# adc_dac_lo.net
KiCad netlist of a schematic drawn in Altium Designer
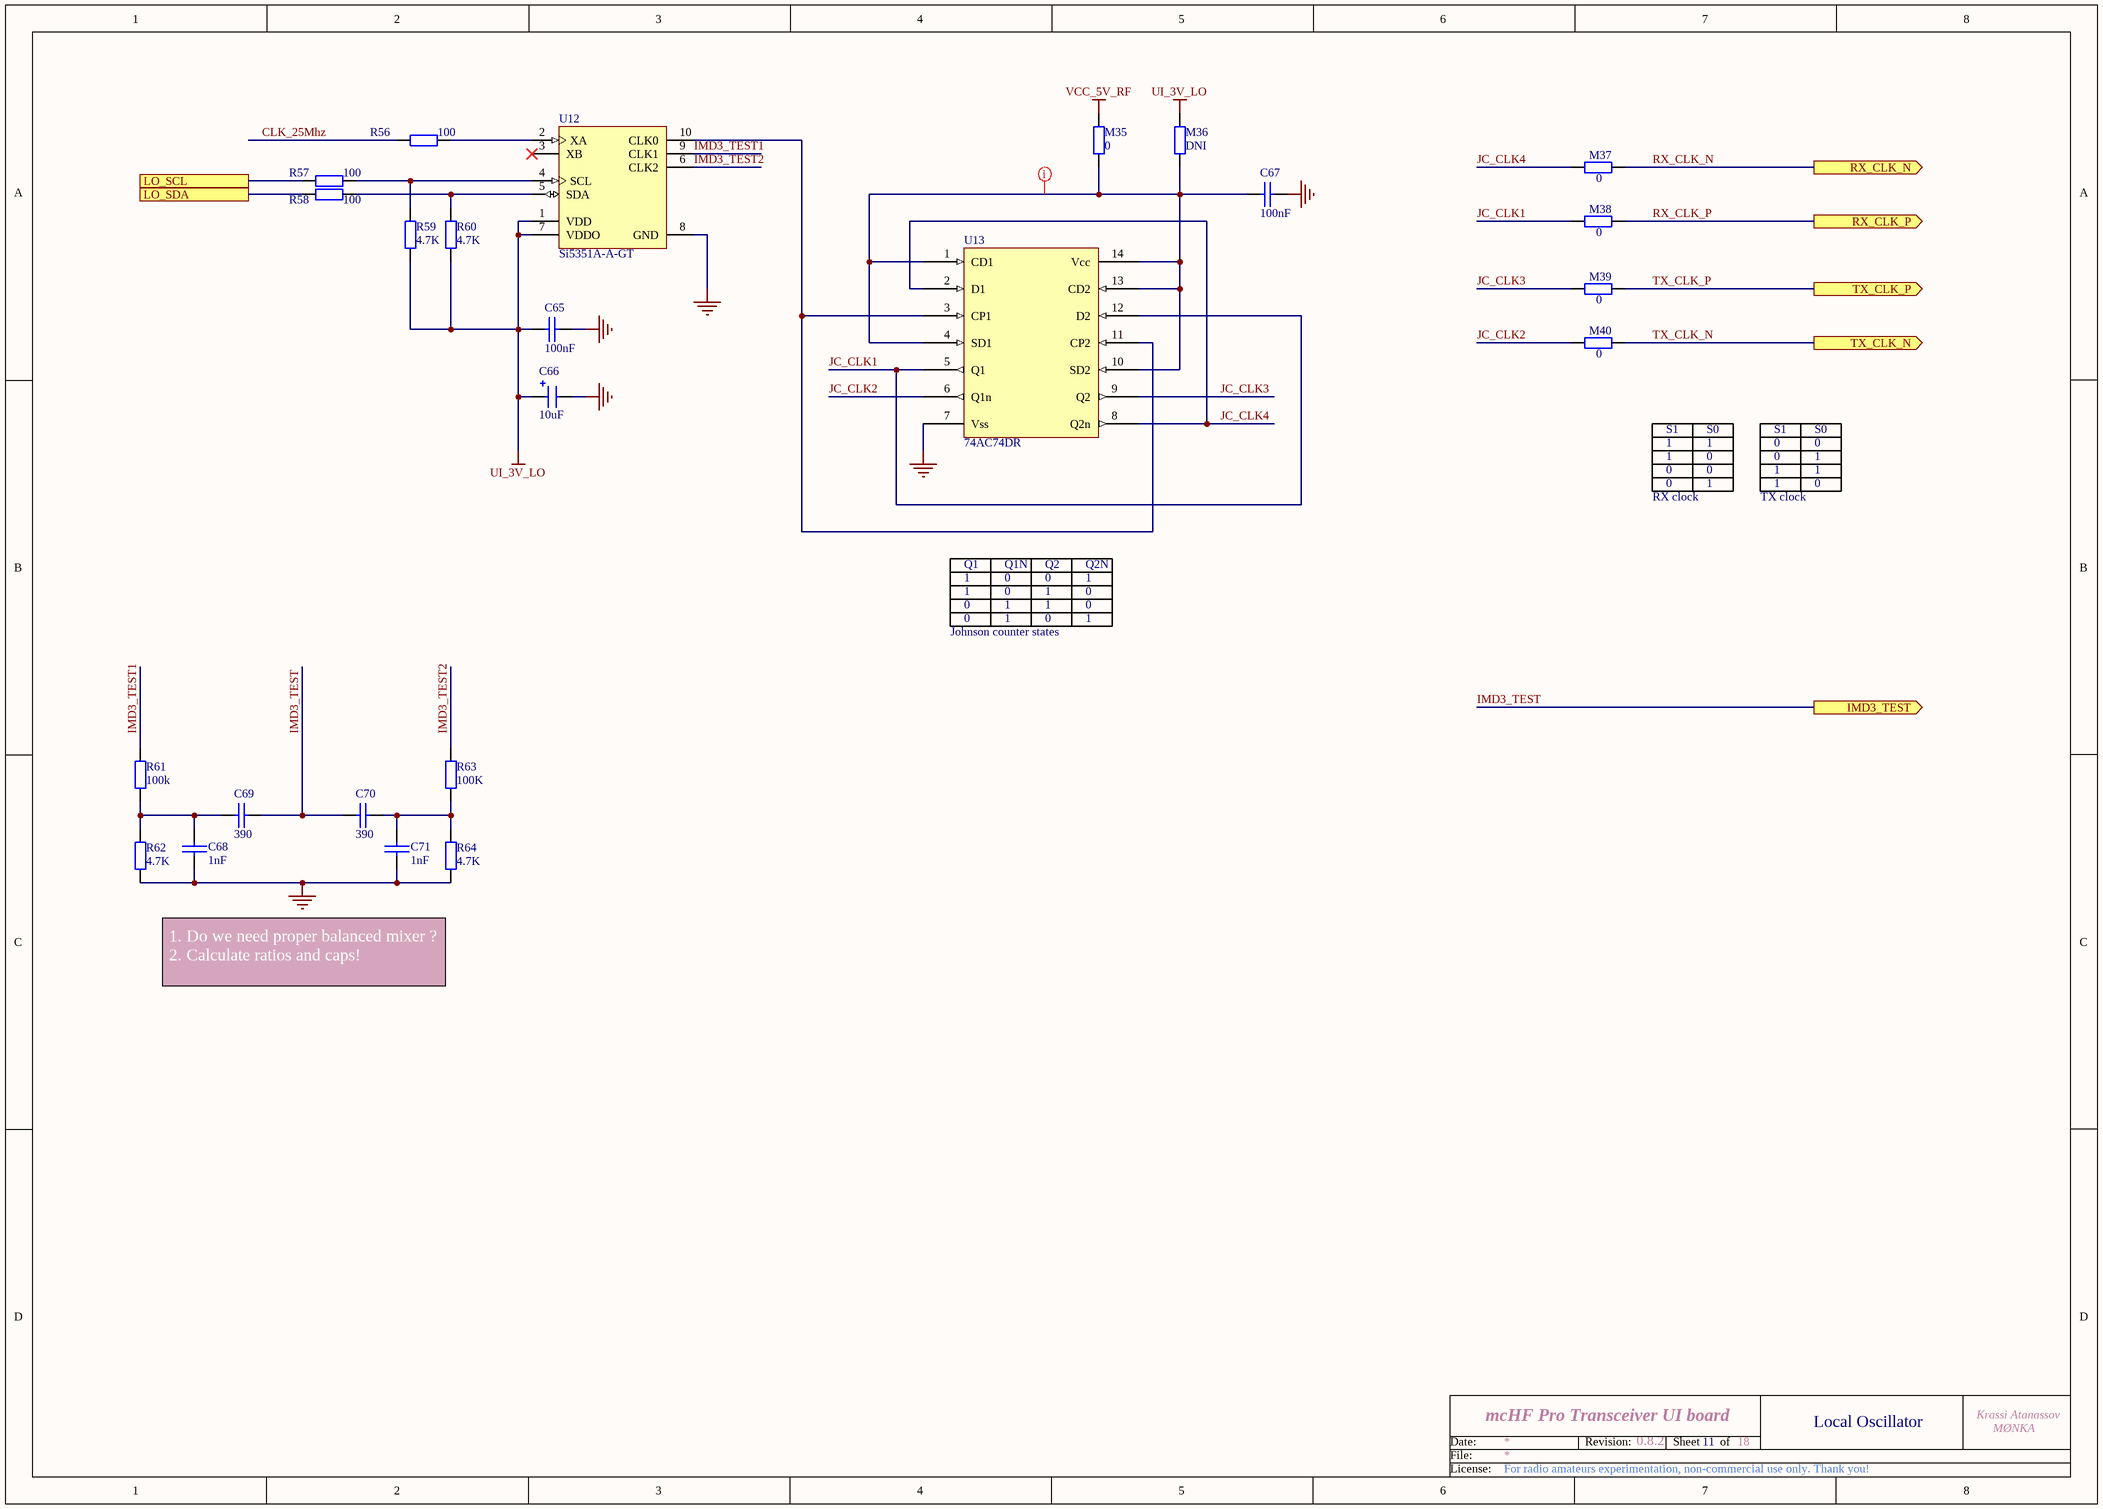
[diagram p0: adc_dac_lo.SchDoc]

(export (version "E")
  (design (tool "Eeschema 10.0.6"))
  (components
    (comp (ref "C65")
      (value "100nF")
      (footprint "0805")
      (description "Capacitor")
      (libsource (lib "*") (part "CAP"))
    )
    (comp (ref "C66")
      (value "10uF")
      (footprint "1206_Elec_Cap")
      (description "Electrolitic capacitor")
      (libsource (lib "*") (part "CAP-POL"))
    )
    (comp (ref "C67")
      (value "100nF")
      (footprint "0805")
      (description "Capacitor")
      (libsource (lib "*") (part "CAP"))
    )
    (comp (ref "C68")
      (value "1nF")
      (footprint "0805")
      (description "Capacitor")
      (libsource (lib "mcHF_ui") (part "CAP"))
    )
    (comp (ref "C69")
      (value "390")
      (footprint "0805")
      (description "Capacitor")
      (libsource (lib "mcHF_rf") (part "CAP"))
    )
    (comp (ref "C70")
      (value "390")
      (footprint "0805")
      (description "Capacitor")
      (libsource (lib "mcHF_rf") (part "CAP"))
    )
    (comp (ref "C71")
      (value "1nF")
      (footprint "0805")
      (description "Capacitor")
      (libsource (lib "mcHF_ui") (part "CAP"))
    )
    (comp (ref "M35")
      (value "0")
      (footprint "0805")
      (description "Resistor")
      (libsource (lib "mcHF_rf") (part "RES"))
    )
    (comp (ref "M36")
      (value "DNI")
      (footprint "0805")
      (description "Resistor")
      (libsource (lib "mcHF_rf") (part "RES"))
    )
    (comp (ref "M37")
      (value "0")
      (footprint "0805")
      (description "Resistor")
      (libsource (lib "") (part "RES_1"))
    )
    (comp (ref "M38")
      (value "0")
      (footprint "0805")
      (description "Resistor")
      (libsource (lib "") (part "RES_1"))
    )
    (comp (ref "M39")
      (value "0")
      (footprint "0805")
      (description "Resistor")
      (libsource (lib "") (part "RES_1"))
    )
    (comp (ref "M40")
      (value "0")
      (footprint "0805")
      (description "Resistor")
      (libsource (lib "") (part "RES_1"))
    )
    (comp (ref "R56")
      (value "100")
      (footprint "0805")
      (description "Resistor")
      (libsource (lib "*") (part "RES"))
    )
    (comp (ref "R57")
      (value "100")
      (footprint "0805")
      (description "Resistor")
      (libsource (lib "*") (part "RES"))
    )
    (comp (ref "R58")
      (value "100")
      (footprint "0805")
      (description "Resistor")
      (libsource (lib "*") (part "RES"))
    )
    (comp (ref "R59")
      (value "4.7K")
      (footprint "0805")
      (description "Resistor")
      (libsource (lib "") (part "RES_1"))
    )
    (comp (ref "R60")
      (value "4.7K")
      (footprint "0805")
      (description "Resistor")
      (libsource (lib "") (part "RES_1"))
    )
    (comp (ref "R61")
      (value "100k")
      (footprint "0805")
      (description "Resistor")
      (libsource (lib "") (part "RES_1"))
    )
    (comp (ref "R62")
      (value "4.7K")
      (footprint "0805")
      (description "Resistor")
      (libsource (lib "") (part "RES_1"))
    )
    (comp (ref "R63")
      (value "100K")
      (footprint "0805")
      (description "Resistor")
      (libsource (lib "") (part "RES_1"))
    )
    (comp (ref "R64")
      (value "4.7K")
      (footprint "0805")
      (description "Resistor")
      (libsource (lib "") (part "RES_1"))
    )
    (comp (ref "U12")
      (value "Si5351A-A-GT")
      (footprint "SLAB-MSOP-10_N")
      (fields (field (name "MANUFACTURER") "Silicon Labs"))
      (libsource (lib "Silicon Labs Clocks and Oscillators") (part "Si5351A-A-GT"))
    )
    (comp (ref "U13")
      (value "74AC74DR")
      (footprint "SO-14")
      (description "Low Voltage Dual D-Type Positive Edge-Triggered  Flip-Flop with 5V Tolerant Inputs")
      (libsource (lib "*") (part "74LCX74M"))
    )
  )
  (nets
    (net (code "1") (name "/CLK_25Mhz") (class "Default")
      (node (ref "R56") (pin "2") (pinfunction "2_2") (pintype "passive"))
    )
    (net (code "2") (name "/IMD3_TEST") (class "Default")
      (node (ref "C69") (pin "1") (pinfunction "1_1") (pintype "passive"))
      (node (ref "C70") (pin "2") (pinfunction "2_2") (pintype "passive"))
    )
    (net (code "3") (name "/IMD3_TEST1") (class "Default")
      (node (ref "R61") (pin "1") (pinfunction "1_1") (pintype "passive"))
      (node (ref "U12") (pin "9") (pinfunction "CLK1_9") (pintype "tri_state"))
    )
    (net (code "4") (name "/IMD3_TEST2") (class "Default")
      (node (ref "R63") (pin "1") (pinfunction "1_1") (pintype "passive"))
      (node (ref "U12") (pin "6") (pinfunction "CLK2_6") (pintype "tri_state"))
    )
    (net (code "5") (name "/JC_CLK1") (class "Default")
      (node (ref "M38") (pin "2") (pinfunction "2_2") (pintype "passive"))
      (node (ref "U13") (pin "12") (pinfunction "D2_12") (pintype "input"))
      (node (ref "U13") (pin "5") (pinfunction "Q1_5") (pintype "output"))
    )
    (net (code "6") (name "/JC_CLK2") (class "Default")
      (node (ref "M40") (pin "2") (pinfunction "2_2") (pintype "passive"))
      (node (ref "U13") (pin "6") (pinfunction "Q1n_6") (pintype "output"))
    )
    (net (code "7") (name "/JC_CLK3") (class "Default")
      (node (ref "M39") (pin "2") (pinfunction "2_2") (pintype "passive"))
      (node (ref "U13") (pin "9") (pinfunction "Q2_9") (pintype "output"))
    )
    (net (code "8") (name "/JC_CLK4") (class "Default")
      (node (ref "M37") (pin "2") (pinfunction "2_2") (pintype "passive"))
      (node (ref "U13") (pin "2") (pinfunction "D1_2") (pintype "input"))
      (node (ref "U13") (pin "8") (pinfunction "Q2n_8") (pintype "output"))
    )
    (net (code "9") (name "/LO_SCL") (class "Default")
      (node (ref "R57") (pin "2") (pinfunction "2_2") (pintype "passive"))
    )
    (net (code "10") (name "/LO_SDA") (class "Default")
      (node (ref "R58") (pin "2") (pinfunction "2_2") (pintype "passive"))
    )
    (net (code "11") (name "/RX_CLK_N") (class "Default")
      (node (ref "M37") (pin "1") (pinfunction "1_1") (pintype "passive"))
    )
    (net (code "12") (name "/RX_CLK_P") (class "Default")
      (node (ref "M38") (pin "1") (pinfunction "1_1") (pintype "passive"))
    )
    (net (code "13") (name "/TX_CLK_N") (class "Default")
      (node (ref "M40") (pin "1") (pinfunction "1_1") (pintype "passive"))
    )
    (net (code "14") (name "/TX_CLK_P") (class "Default")
      (node (ref "M39") (pin "1") (pinfunction "1_1") (pintype "passive"))
    )
    (net (code "15") (name "GND") (class "Default")
      (node (ref "C65") (pin "2") (pinfunction "2_2") (pintype "passive"))
      (node (ref "C66") (pin "2") (pinfunction "2_2") (pintype "passive"))
      (node (ref "C67") (pin "1") (pinfunction "1_1") (pintype "passive"))
      (node (ref "C68") (pin "2") (pinfunction "2_2") (pintype "passive"))
      (node (ref "C71") (pin "2") (pinfunction "2_2") (pintype "passive"))
      (node (ref "R62") (pin "2") (pinfunction "2_2") (pintype "passive"))
      (node (ref "R64") (pin "2") (pinfunction "2_2") (pintype "passive"))
      (node (ref "U12") (pin "8") (pinfunction "GND_8") (pintype "power_in"))
      (node (ref "U13") (pin "7") (pinfunction "Vss_7") (pintype "power_in"))
    )
    (net (code "16") (name "Net-(C68-Pad1)") (class "Default")
      (node (ref "C68") (pin "1") (pinfunction "1_1") (pintype "passive"))
      (node (ref "C69") (pin "2") (pinfunction "2_2") (pintype "passive"))
      (node (ref "R61") (pin "2") (pinfunction "2_2") (pintype "passive"))
      (node (ref "R62") (pin "1") (pinfunction "1_1") (pintype "passive"))
    )
    (net (code "17") (name "Net-(C70-Pad1)") (class "Default")
      (node (ref "C70") (pin "1") (pinfunction "1_1") (pintype "passive"))
      (node (ref "C71") (pin "1") (pinfunction "1_1") (pintype "passive"))
      (node (ref "R63") (pin "2") (pinfunction "2_2") (pintype "passive"))
      (node (ref "R64") (pin "1") (pinfunction "1_1") (pintype "passive"))
    )
    (net (code "18") (name "Net-(U12-CLK0)") (class "Default")
      (node (ref "U12") (pin "10") (pinfunction "CLK0_10") (pintype "tri_state"))
      (node (ref "U13") (pin "11") (pinfunction "CP2_11") (pintype "input"))
      (node (ref "U13") (pin "3") (pinfunction "CP1_3") (pintype "input"))
    )
    (net (code "19") (name "Net-(U12-SCL)") (class "Default")
      (node (ref "R57") (pin "1") (pinfunction "1_1") (pintype "passive"))
      (node (ref "R59") (pin "1") (pinfunction "1_1") (pintype "passive"))
      (node (ref "U12") (pin "4") (pinfunction "SCL_4") (pintype "input"))
    )
    (net (code "20") (name "Net-(U12-SDA)") (class "Default")
      (node (ref "R58") (pin "1") (pinfunction "1_1") (pintype "passive"))
      (node (ref "R60") (pin "1") (pinfunction "1_1") (pintype "passive"))
      (node (ref "U12") (pin "5") (pinfunction "SDA_5") (pintype "bidirectional"))
    )
    (net (code "21") (name "Net-(U12-XA)") (class "Default")
      (node (ref "R56") (pin "1") (pinfunction "1_1") (pintype "passive"))
      (node (ref "U12") (pin "2") (pinfunction "XA_2") (pintype "input"))
    )
    (net (code "22") (name "Net-(U13-CD1)") (class "Default")
      (node (ref "C67") (pin "2") (pinfunction "2_2") (pintype "passive"))
      (node (ref "M35") (pin "1") (pinfunction "1_1") (pintype "passive"))
      (node (ref "M36") (pin "1") (pinfunction "1_1") (pintype "passive"))
      (node (ref "U13") (pin "1") (pinfunction "CD1_1") (pintype "input"))
      (node (ref "U13") (pin "10") (pinfunction "SD2_10") (pintype "input"))
      (node (ref "U13") (pin "13") (pinfunction "CD2_13") (pintype "input"))
      (node (ref "U13") (pin "14") (pinfunction "Vcc_14") (pintype "power_in"))
      (node (ref "U13") (pin "4") (pinfunction "SD1_4") (pintype "input"))
    )
    (net (code "23") (name "UI_3V_LO") (class "Default")
      (node (ref "C65") (pin "1") (pinfunction "1_1") (pintype "passive"))
      (node (ref "C66") (pin "1") (pinfunction "1_1") (pintype "passive"))
      (node (ref "M36") (pin "2") (pinfunction "2_2") (pintype "passive"))
      (node (ref "R59") (pin "2") (pinfunction "2_2") (pintype "passive"))
      (node (ref "R60") (pin "2") (pinfunction "2_2") (pintype "passive"))
      (node (ref "U12") (pin "1") (pinfunction "VDD_1") (pintype "power_in"))
      (node (ref "U12") (pin "7") (pinfunction "VDDO_7") (pintype "power_in"))
    )
    (net (code "24") (name "VCC_5V_RF") (class "Default")
      (node (ref "M35") (pin "2") (pinfunction "2_2") (pintype "passive"))
    )
    (net (code "25") (name "unconnected-(U12-XB-Pad3)") (class "Default")
      (node (ref "U12") (pin "3") (pinfunction "XB_3") (pintype "passive+no_connect"))
    )
  )
)
